# BOWIE_POWER.net
KiCad netlist of a schematic drawn in Altium Designer
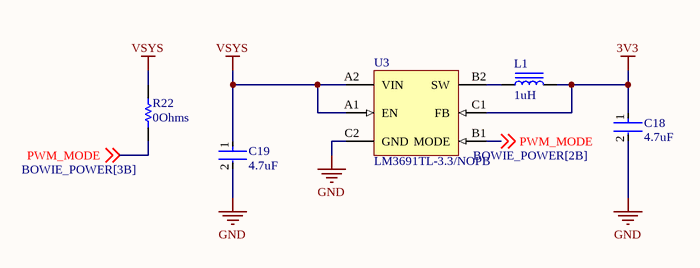
[diagram p0: BOWIE_POWER.SchDoc]

(export (version "E")
  (design (tool "Eeschema 10.0.6"))
  (components
    (comp (ref "C18")
      (value "4.7uF")
      (footprint "FP-CL828-IPC_C")
      (description "Cap Ceramic 4.7uF 10V X5R ±10% SMD 0402 +85°C Paper T/R")
      (fields (field (name "TOLERANCE") "10%"))
      (libsource (lib "Altium Content Vault") (part "b4654b650e69147ec39a6b967a45e02"))
    )
    (comp (ref "C19")
      (value "4.7uF")
      (footprint "FP-CL828-IPC_C")
      (description "Cap Ceramic 4.7uF 10V X5R ±10% SMD 0402 +85°C Paper T/R")
      (fields (field (name "TOLERANCE") "10%"))
      (libsource (lib "Altium Content Vault") (part "b4654b650e69147ec39a6b967a45e02"))
    )
    (comp (ref "L1")
      (value "1uH")
      (footprint "IND 0603_1608 RF WW")
      (description "SMT Inductor")
      (fields (field (name "MANUFACTURER") "Taiyo Yuden") (field (name "PART NUMBER") "MCHK1608T1R0MKN"))
      (libsource (lib "Phalanx") (part "MCHK1608T1R0MKN"))
    )
    (comp (ref "R22")
      (value "0Ohms")
      (footprint "RESC1005X40X25ML05T10")
      (fields (field (name "PART NUMBER") "CRCW040210K0FKEDHP") (field (name "MANUFACTURER") "Vishay Dale"))
      (libsource (lib "Altium Content Vault") (part "RES"))
    )
    (comp (ref "U3")
      (value "LM3691TL-3.3/NOPB")
      (footprint "YZR0006APAF")
      (fields (field (name "MANUFACTURER") "Texas Instruments"))
      (libsource (lib "Altium Content Vault") (part "PM-DCDC-LM3691-6"))
    )
  )
  (nets
    (net (code "1") (name "3V3") (class "Default")
      (node (ref "C18") (pin "1") (pinfunction "1_1") (pintype "passive"))
      (node (ref "L1") (pin "2") (pinfunction "2_2") (pintype "passive"))
      (node (ref "U3") (pin "C1") (pinfunction "FB_C1") (pintype "input"))
    )
    (net (code "2") (name "GND") (class "Default")
      (node (ref "C18") (pin "2") (pinfunction "2_2") (pintype "passive"))
      (node (ref "C19") (pin "2") (pinfunction "2_2") (pintype "passive"))
      (node (ref "U3") (pin "C2") (pinfunction "GND_C2") (pintype "power_in"))
    )
    (net (code "3") (name "Net-(U3-SW)") (class "Default")
      (node (ref "L1") (pin "1") (pinfunction "1_1") (pintype "passive"))
      (node (ref "U3") (pin "B2") (pinfunction "SW_B2") (pintype "power_in"))
    )
    (net (code "4") (name "PWM_MODE") (class "Default")
      (node (ref "R22") (pin "2") (pinfunction "2_2") (pintype "passive"))
      (node (ref "U3") (pin "B1") (pinfunction "MODE_B1") (pintype "input"))
    )
    (net (code "5") (name "VSYS") (class "Default")
      (node (ref "C19") (pin "1") (pinfunction "1_1") (pintype "passive"))
      (node (ref "R22") (pin "1") (pinfunction "1_1") (pintype "passive"))
      (node (ref "U3") (pin "A1") (pinfunction "EN_A1") (pintype "input"))
      (node (ref "U3") (pin "A2") (pinfunction "VIN_A2") (pintype "power_in"))
    )
  )
)
